# prog-E01.net
KiCad netlist of a schematic drawn in EAGLE
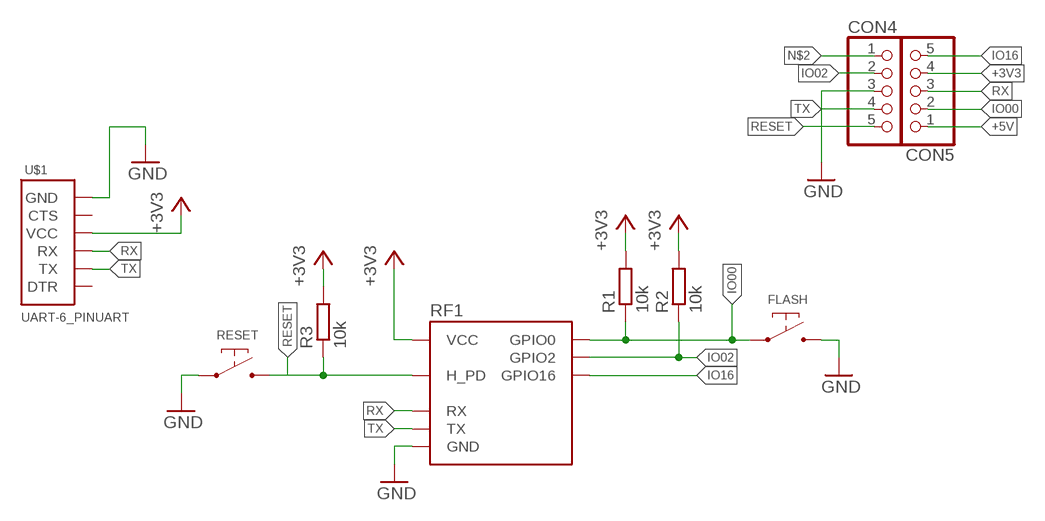
[diagram p0: schematic, sheet 1]

(export (version "E")
  (design (tool "Eeschema 10.0.6"))
  (components
    (comp (ref "CON4")
      (value "GENERIC-1X5")
      (footprint "eagle-import:PINHEADER-100MIL-1X5-NOSILK")
      (libsource (lib "eagle-import") (part "GENERIC-1X5"))
    )
    (comp (ref "CON5")
      (value "GENERIC-1X5")
      (footprint "eagle-import:PINHEADER-100MIL-1X5-NOSILK")
      (libsource (lib "eagle-import") (part "GENERIC-1X5"))
    )
    (comp (ref "FLASH")
      (value "SWITCH-DEFAULT_OFF-SMD-2_PIN")
      (footprint "eagle-import:SWITCH-SMD-2_PIN-DX")
      (libsource (lib "eagle-import") (part "SWITCH-DEFAULT_OFF-SMD-2_PIN"))
    )
    (comp (ref "R1")
      (value "10k")
      (footprint "eagle-import:R0603")
      (libsource (lib "eagle-import") (part "R-EU_R0603"))
    )
    (comp (ref "R2")
      (value "10k")
      (footprint "eagle-import:R0603")
      (libsource (lib "eagle-import") (part "R-EU_R0603"))
    )
    (comp (ref "R3")
      (value "10k")
      (footprint "eagle-import:R0603")
      (libsource (lib "eagle-import") (part "R-EU_R0603"))
    )
    (comp (ref "RESET")
      (value "SWITCH-DEFAULT_OFF-SMD-2_PIN")
      (footprint "eagle-import:SWITCH-SMD-2_PIN-DX")
      (libsource (lib "eagle-import") (part "SWITCH-DEFAULT_OFF-SMD-2_PIN"))
    )
    (comp (ref "RF1")
      (value "ESP2866-ESP-01THT-NOSILK")
      (footprint "eagle-import:ESP8266-ESP-01-NOSILK")
      (libsource (lib "eagle-import") (part "ESP2866-ESP-01THT-NOSILK"))
    )
    (comp (ref "U$1")
      (value "UART-6_PINUART")
      (footprint "eagle-import:ANGLE-1X6")
      (libsource (lib "eagle-import") (part "UART-6_PINUART"))
    )
  )
  (nets
    (net (code "1") (name "+3V3") (class "Default")
      (node (ref "CON5") (pin "4") (pinfunction "4_4") (pintype "passive"))
      (node (ref "R1") (pin "2") (pinfunction "2_2") (pintype "passive"))
      (node (ref "R2") (pin "2") (pinfunction "2_2") (pintype "passive"))
      (node (ref "R3") (pin "2") (pinfunction "2_2") (pintype "passive"))
      (node (ref "RF1") (pin "VCC") (pinfunction "VCC_VCC") (pintype "bidirectional"))
      (node (ref "U$1") (pin "3") (pinfunction "VCC_3") (pintype "bidirectional"))
    )
    (net (code "2") (name "+5V") (class "Default")
      (node (ref "CON5") (pin "1") (pinfunction "1_1") (pintype "passive"))
    )
    (net (code "3") (name "GND") (class "Default")
      (node (ref "CON4") (pin "3") (pinfunction "3_3") (pintype "passive"))
      (node (ref "FLASH") (pin "P$2") (pinfunction "P$2_P$2") (pintype "bidirectional"))
      (node (ref "RESET") (pin "P$1") (pinfunction "P$1_P$1") (pintype "bidirectional"))
      (node (ref "RF1") (pin "GND") (pinfunction "GND_GND") (pintype "bidirectional"))
      (node (ref "U$1") (pin "1") (pinfunction "GND_1") (pintype "bidirectional"))
    )
    (net (code "4") (name "IO00") (class "Default")
      (node (ref "CON5") (pin "2") (pinfunction "2_2") (pintype "passive"))
      (node (ref "FLASH") (pin "P$1") (pinfunction "P$1_P$1") (pintype "bidirectional"))
      (node (ref "R1") (pin "1") (pinfunction "1_1") (pintype "passive"))
      (node (ref "RF1") (pin "GPIO0") (pinfunction "GPIO0_GPIO0") (pintype "bidirectional"))
    )
    (net (code "5") (name "IO02") (class "Default")
      (node (ref "CON4") (pin "2") (pinfunction "2_2") (pintype "passive"))
      (node (ref "R2") (pin "1") (pinfunction "1_1") (pintype "passive"))
      (node (ref "RF1") (pin "GPIO2") (pinfunction "GPIO2_GPIO2") (pintype "bidirectional"))
    )
    (net (code "6") (name "IO16") (class "Default")
      (node (ref "CON5") (pin "5") (pinfunction "5_5") (pintype "passive"))
      (node (ref "RF1") (pin "GPIO16") (pinfunction "GPIO16_GPIO16") (pintype "bidirectional"))
    )
    (net (code "7") (name "N$2") (class "Default")
      (node (ref "CON4") (pin "1") (pinfunction "1_1") (pintype "passive"))
    )
    (net (code "8") (name "RESET") (class "Default")
      (node (ref "CON4") (pin "5") (pinfunction "5_5") (pintype "passive"))
      (node (ref "R3") (pin "1") (pinfunction "1_1") (pintype "passive"))
      (node (ref "RESET") (pin "P$2") (pinfunction "P$2_P$2") (pintype "bidirectional"))
      (node (ref "RF1") (pin "H_PD") (pinfunction "H_PD_H_PD") (pintype "bidirectional"))
    )
    (net (code "9") (name "RX") (class "Default")
      (node (ref "CON5") (pin "3") (pinfunction "3_3") (pintype "passive"))
      (node (ref "RF1") (pin "RX") (pinfunction "RX_RX") (pintype "bidirectional"))
      (node (ref "U$1") (pin "4") (pinfunction "RX_4") (pintype "bidirectional"))
    )
    (net (code "10") (name "TX") (class "Default")
      (node (ref "CON4") (pin "4") (pinfunction "4_4") (pintype "passive"))
      (node (ref "RF1") (pin "TX") (pinfunction "TX_TX") (pintype "bidirectional"))
      (node (ref "U$1") (pin "5") (pinfunction "TX_5") (pintype "bidirectional"))
    )
    (net (code "11") (name "unconnected-(U$1-CTS-Pad2)") (class "Default")
      (node (ref "U$1") (pin "2") (pinfunction "CTS_2") (pintype "bidirectional"))
    )
    (net (code "12") (name "unconnected-(U$1-DTR-Pad6)") (class "Default")
      (node (ref "U$1") (pin "6") (pinfunction "DTR_6") (pintype "bidirectional"))
    )
  )
)
